# rev-polarity-deflector-dish-mk-1_0.net
KiCad netlist of a schematic drawn in EAGLE
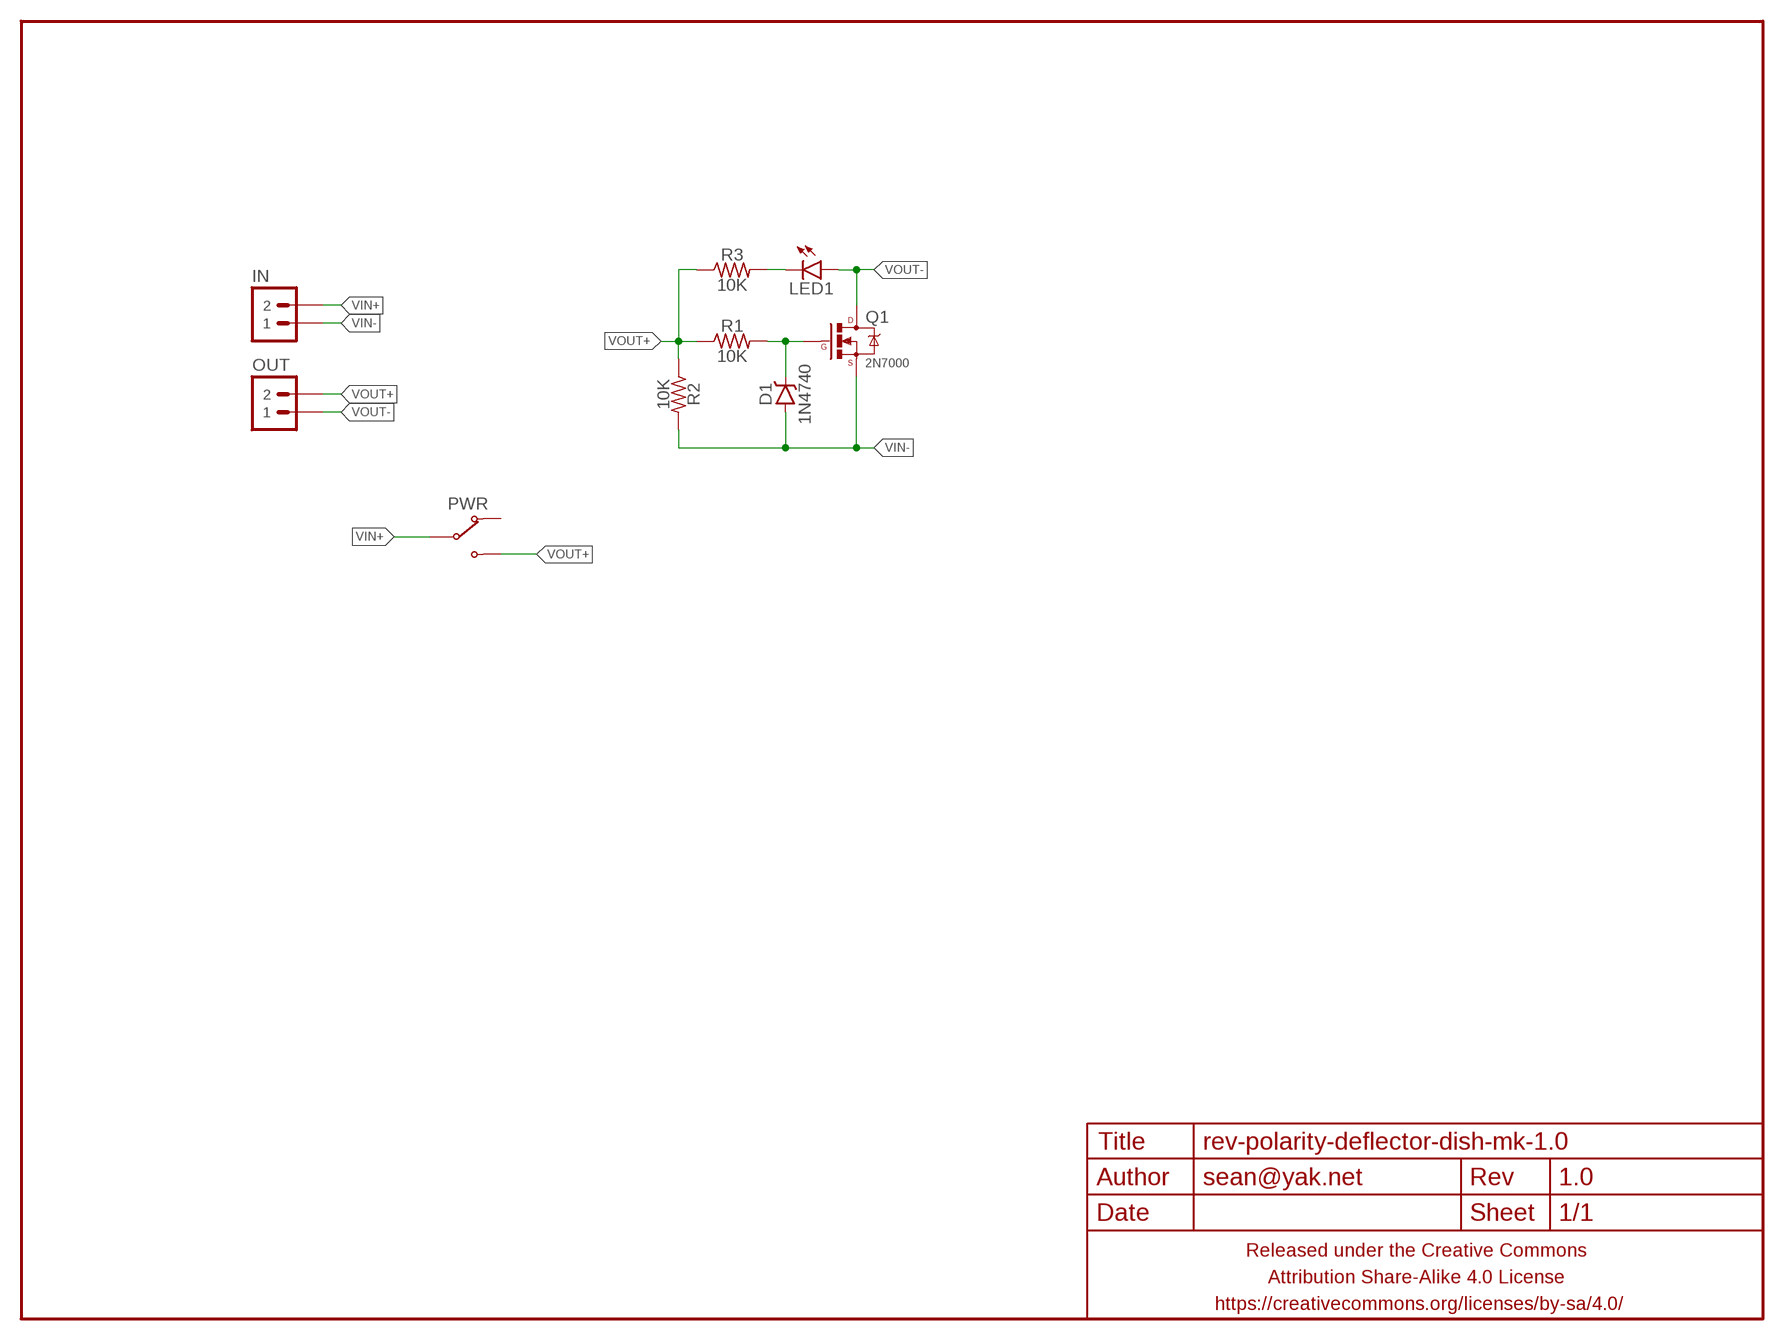
[diagram p0: schematic, sheet 1]

(export (version "E")
  (design (tool "Eeschema 10.0.6"))
  (components
    (comp (ref "D1")
      (value "1N4740")
      (footprint "eagle-import:DIODE-ZENNER-7.62MM")
      (libsource (lib "eagle-import") (part "DIODE-ZENER7.62MM-PTH"))
    )
    (comp (ref "FRAME1")
      (value "FRAME-LETTERNO_PACKAGE")
      (footprint "eagle-import:DUMMY")
      (fields (field (name "DESIGNER") "sean@yak.net") (field (name "VERSION") "1.0"))
      (libsource (lib "eagle-import") (part "FRAME-LETTERNO_PACKAGE"))
    )
    (comp (ref "IN")
      (value "M02PTH-CENTERED-R+")
      (footprint "eagle-import:1X02-CENTER-R+")
      (libsource (lib "eagle-import") (part "M02PTH-CENTERED-R+"))
    )
    (comp (ref "LED1")
      (value "LED3MM-LESS")
      (footprint "eagle-import:LED3MM-LESSSILK")
      (libsource (lib "eagle-import") (part "LED3MM-LESS"))
    )
    (comp (ref "OUT")
      (value "M02PTH-CENTERED-R+")
      (footprint "eagle-import:1X02-CENTER-R+")
      (libsource (lib "eagle-import") (part "M02PTH-CENTERED-R+"))
    )
    (comp (ref "PWR")
      (value "SWITCH-SPDTPTH-VERT-2.54MM")
      (footprint "eagle-import:SWITCH-SPDT")
      (libsource (lib "eagle-import") (part "SWITCH-SPDTPTH-VERT-2.54MM"))
    )
    (comp (ref "Q1")
      (value "2N7000")
      (footprint "eagle-import:TO-92-AMMO")
      (libsource (lib "eagle-import") (part "MOSFET-NCHANNEL2N7000-AMMO"))
    )
    (comp (ref "R1")
      (value "10K")
      (footprint "eagle-import:RESISTOR-AXIAL-PTH-7.62MM")
      (libsource (lib "eagle-import") (part "RESISTORPTH-AXIAL-7.62MM"))
    )
    (comp (ref "R2")
      (value "10K")
      (footprint "eagle-import:RESISTOR-AXIAL-PTH-7.62MM")
      (libsource (lib "eagle-import") (part "RESISTORPTH-AXIAL-7.62MM"))
    )
    (comp (ref "R3")
      (value "10K")
      (footprint "eagle-import:RESISTOR-AXIAL-PTH-7.62MM")
      (libsource (lib "eagle-import") (part "RESISTORPTH-AXIAL-7.62MM"))
    )
  )
  (nets
    (net (code "1") (name "Net-(D1-C)") (class "Default")
      (node (ref "D1") (pin "K") (pinfunction "C_K") (pintype "passive"))
      (node (ref "Q1") (pin "2") (pinfunction "G_2") (pintype "passive"))
      (node (ref "R1") (pin "P$2") (pinfunction "2_P$2") (pintype "passive"))
    )
    (net (code "2") (name "Net-(LED1-C)") (class "Default")
      (node (ref "LED1") (pin "K") (pinfunction "C_K") (pintype "passive"))
      (node (ref "R3") (pin "P$2") (pinfunction "2_P$2") (pintype "passive"))
    )
    (net (code "3") (name "VIN+") (class "Default")
      (node (ref "IN") (pin "2") (pinfunction "2_2") (pintype "passive"))
      (node (ref "PWR") (pin "2") (pinfunction "COM_2") (pintype "passive"))
    )
    (net (code "4") (name "VIN-") (class "Default")
      (node (ref "D1") (pin "A") (pinfunction "A_A") (pintype "passive"))
      (node (ref "IN") (pin "1") (pinfunction "1_1") (pintype "passive"))
      (node (ref "Q1") (pin "1") (pinfunction "S_1") (pintype "passive"))
      (node (ref "R2") (pin "P$2") (pinfunction "2_P$2") (pintype "passive"))
    )
    (net (code "5") (name "VOUT+") (class "Default")
      (node (ref "OUT") (pin "2") (pinfunction "2_2") (pintype "passive"))
      (node (ref "PWR") (pin "3") (pinfunction "NO_3") (pintype "passive"))
      (node (ref "R1") (pin "P$1") (pinfunction "1_P$1") (pintype "passive"))
      (node (ref "R2") (pin "P$1") (pinfunction "1_P$1") (pintype "passive"))
      (node (ref "R3") (pin "P$1") (pinfunction "1_P$1") (pintype "passive"))
    )
    (net (code "6") (name "VOUT-") (class "Default")
      (node (ref "LED1") (pin "A") (pinfunction "A_A") (pintype "passive"))
      (node (ref "OUT") (pin "1") (pinfunction "1_1") (pintype "passive"))
      (node (ref "Q1") (pin "3") (pinfunction "D_3") (pintype "passive"))
    )
    (net (code "7") (name "unconnected-(PWR-NC-Pad1)") (class "Default")
      (node (ref "PWR") (pin "1") (pinfunction "NC_1") (pintype "passive"))
    )
  )
)
